# mSD-Shield_v20.net
KiCad netlist of a schematic drawn in EAGLE
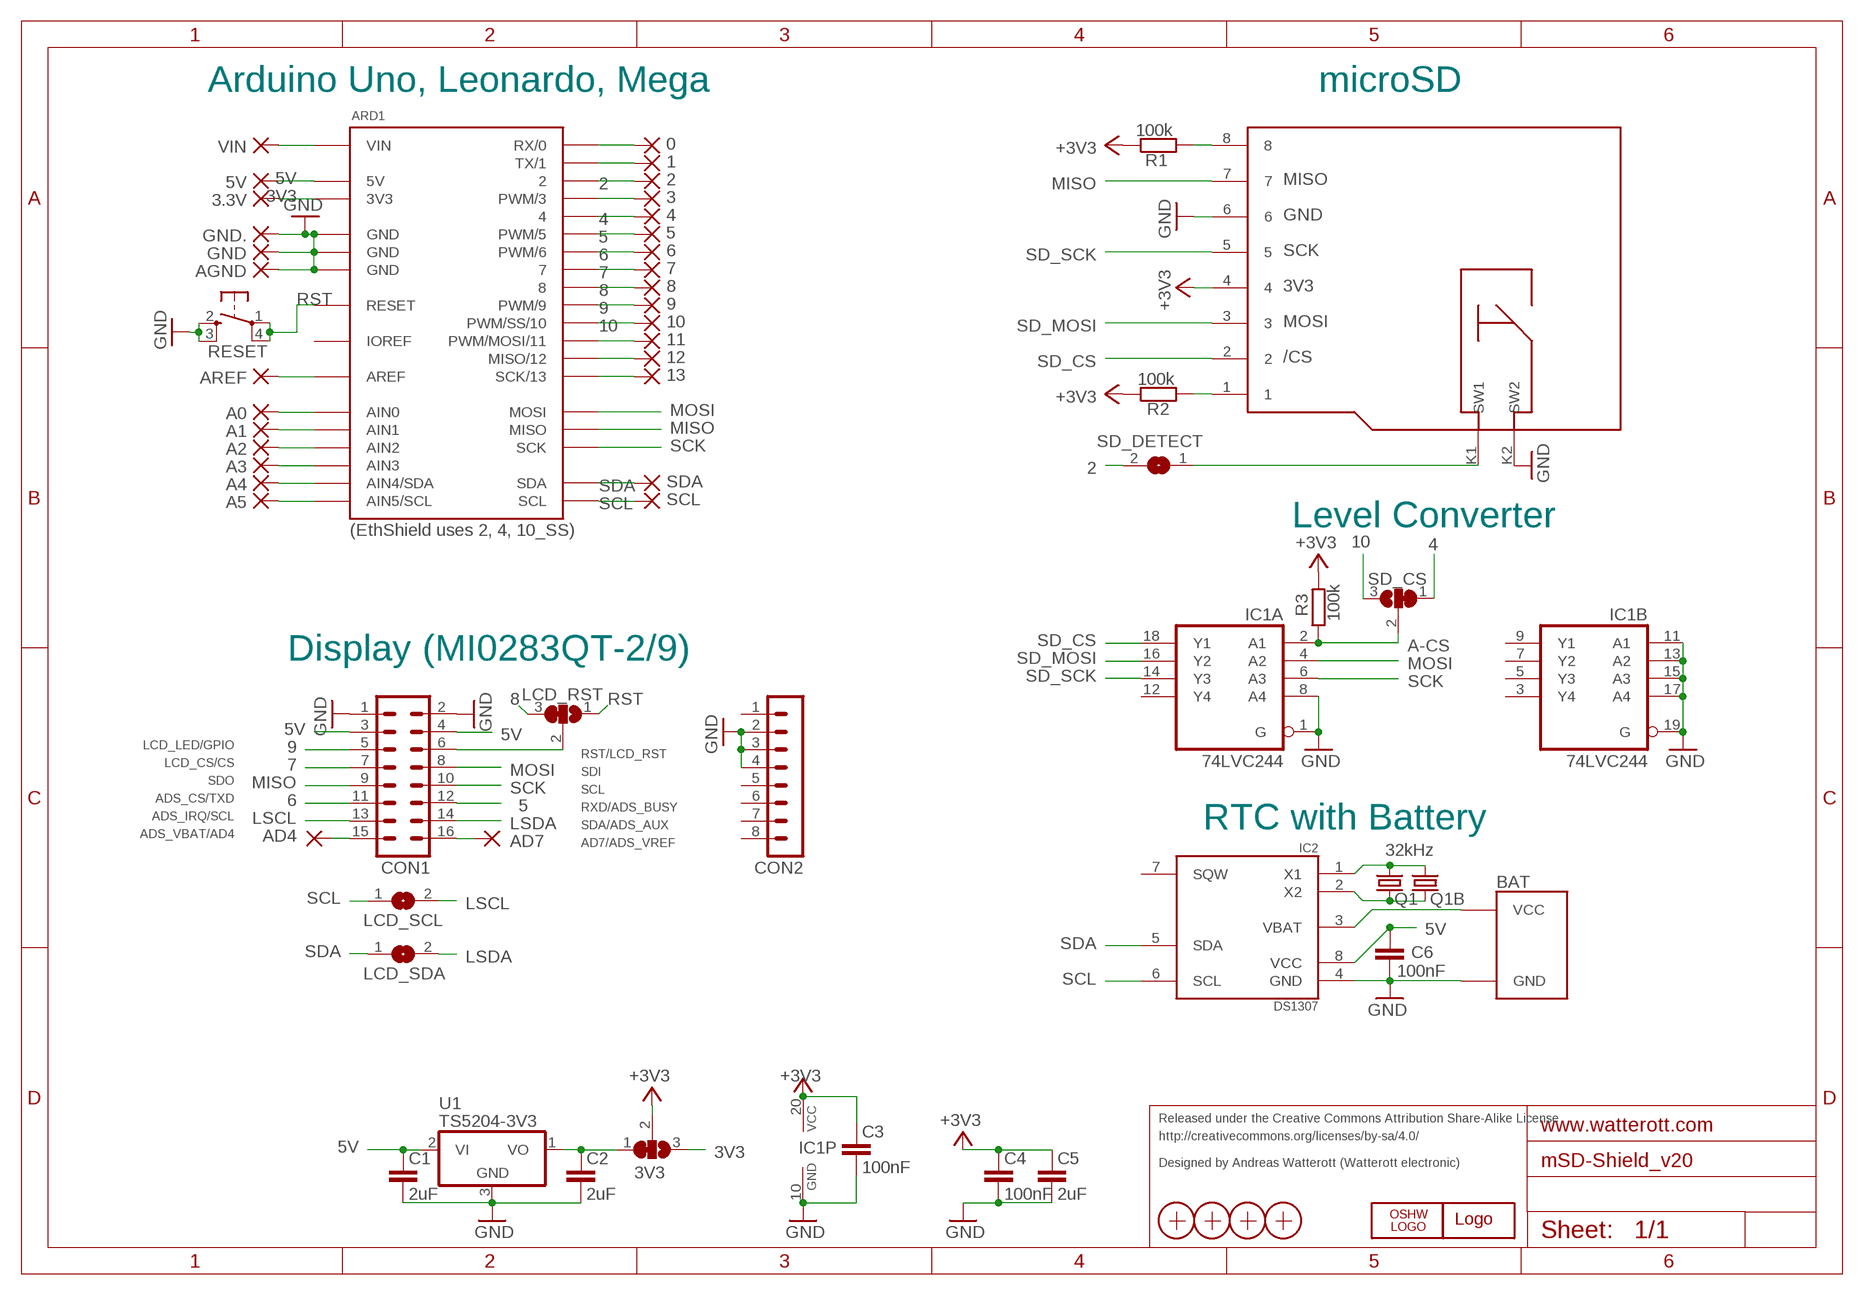
[diagram p0: schematic, sheet 1]

(export (version "E")
  (design (tool "Eeschema 10.0.6"))
  (components
    (comp (ref "0")
      (value "1,6/0,8")
      (footprint "eagle-import:1,6_0,8")
      (libsource (lib "eagle-import") (part "1,6/0,8"))
    )
    (comp (ref "1")
      (value "1,6/0,8")
      (footprint "eagle-import:1,6_0,8")
      (libsource (lib "eagle-import") (part "1,6/0,8"))
    )
    (comp (ref "2")
      (value "1,6/0,8")
      (footprint "eagle-import:1,6_0,8")
      (libsource (lib "eagle-import") (part "1,6/0,8"))
    )
    (comp (ref "3")
      (value "1,6/0,8")
      (footprint "eagle-import:1,6_0,8")
      (libsource (lib "eagle-import") (part "1,6/0,8"))
    )
    (comp (ref "3.3V")
      (value "1,6/0,8")
      (footprint "eagle-import:1,6_0,8")
      (libsource (lib "eagle-import") (part "1,6/0,8"))
    )
    (comp (ref "3V3")
      (value "SJ2W")
      (footprint "eagle-import:SJ_2")
      (libsource (lib "eagle-import") (part "SJ2W"))
    )
    (comp (ref "4")
      (value "1,6/0,8")
      (footprint "eagle-import:1,6_0,8")
      (libsource (lib "eagle-import") (part "1,6/0,8"))
    )
    (comp (ref "5")
      (value "1,6/0,8")
      (footprint "eagle-import:1,6_0,8")
      (libsource (lib "eagle-import") (part "1,6/0,8"))
    )
    (comp (ref "5V")
      (value "1,6/0,8")
      (footprint "eagle-import:1,6_0,8")
      (libsource (lib "eagle-import") (part "1,6/0,8"))
    )
    (comp (ref "6")
      (value "1,6/0,8")
      (footprint "eagle-import:1,6_0,8")
      (libsource (lib "eagle-import") (part "1,6/0,8"))
    )
    (comp (ref "7")
      (value "1,6/0,8")
      (footprint "eagle-import:1,6_0,8")
      (libsource (lib "eagle-import") (part "1,6/0,8"))
    )
    (comp (ref "8")
      (value "1,6/0,8")
      (footprint "eagle-import:1,6_0,8")
      (libsource (lib "eagle-import") (part "1,6/0,8"))
    )
    (comp (ref "9")
      (value "1,6/0,8")
      (footprint "eagle-import:1,6_0,8")
      (libsource (lib "eagle-import") (part "1,6/0,8"))
    )
    (comp (ref "10")
      (value "1,6/0,8")
      (footprint "eagle-import:1,6_0,8")
      (libsource (lib "eagle-import") (part "1,6/0,8"))
    )
    (comp (ref "11")
      (value "1,6/0,8")
      (footprint "eagle-import:1,6_0,8")
      (libsource (lib "eagle-import") (part "1,6/0,8"))
    )
    (comp (ref "12")
      (value "1,6/0,8")
      (footprint "eagle-import:1,6_0,8")
      (libsource (lib "eagle-import") (part "1,6/0,8"))
    )
    (comp (ref "13")
      (value "1,6/0,8")
      (footprint "eagle-import:1,6_0,8")
      (libsource (lib "eagle-import") (part "1,6/0,8"))
    )
    (comp (ref "A0")
      (value "1,6/0,8")
      (footprint "eagle-import:1,6_0,8")
      (libsource (lib "eagle-import") (part "1,6/0,8"))
    )
    (comp (ref "A1")
      (value "1,6/0,8")
      (footprint "eagle-import:1,6_0,8")
      (libsource (lib "eagle-import") (part "1,6/0,8"))
    )
    (comp (ref "A2")
      (value "1,6/0,8")
      (footprint "eagle-import:1,6_0,8")
      (libsource (lib "eagle-import") (part "1,6/0,8"))
    )
    (comp (ref "A3")
      (value "1,6/0,8")
      (footprint "eagle-import:1,6_0,8")
      (libsource (lib "eagle-import") (part "1,6/0,8"))
    )
    (comp (ref "A4")
      (value "1,6/0,8")
      (footprint "eagle-import:1,6_0,8")
      (libsource (lib "eagle-import") (part "1,6/0,8"))
    )
    (comp (ref "A5")
      (value "1,6/0,8")
      (footprint "eagle-import:1,6_0,8")
      (libsource (lib "eagle-import") (part "1,6/0,8"))
    )
    (comp (ref "AD4")
      (value "1,6/0,8")
      (footprint "eagle-import:1,6_0,8")
      (libsource (lib "eagle-import") (part "1,6/0,8"))
    )
    (comp (ref "AD7")
      (value "1,6/0,8")
      (footprint "eagle-import:1,6_0,8")
      (libsource (lib "eagle-import") (part "1,6/0,8"))
    )
    (comp (ref "AGND")
      (value "1,6/0,8")
      (footprint "eagle-import:1,6_0,8")
      (libsource (lib "eagle-import") (part "1,6/0,8"))
    )
    (comp (ref "ARD1")
      (value "UNO_ISP2")
      (footprint "eagle-import:UNO_ISP2")
      (libsource (lib "eagle-import") (part "UNO_ISP2"))
    )
    (comp (ref "AREF")
      (value "1,6/0,8")
      (footprint "eagle-import:1,6_0,8")
      (libsource (lib "eagle-import") (part "1,6/0,8"))
    )
    (comp (ref "BAT")
      (value "4UC-05581")
      (footprint "eagle-import:4UC-05581")
      (libsource (lib "eagle-import") (part "4UC-05581"))
    )
    (comp (ref "C1")
      (value "2uF")
      (footprint "eagle-import:C0805")
      (libsource (lib "eagle-import") (part "C-EUC0805"))
    )
    (comp (ref "C2")
      (value "2uF")
      (footprint "eagle-import:C0805")
      (libsource (lib "eagle-import") (part "C-EUC0805"))
    )
    (comp (ref "C3")
      (value "100nF")
      (footprint "eagle-import:C0603")
      (libsource (lib "eagle-import") (part "C-EUC0603"))
    )
    (comp (ref "C4")
      (value "100nF")
      (footprint "eagle-import:C0603")
      (libsource (lib "eagle-import") (part "C-EUC0603"))
    )
    (comp (ref "C5")
      (value "2uF")
      (footprint "eagle-import:C0603")
      (libsource (lib "eagle-import") (part "C-EUC0603"))
    )
    (comp (ref "C6")
      (value "100nF")
      (footprint "eagle-import:C0603")
      (libsource (lib "eagle-import") (part "C-EUC0603"))
    )
    (comp (ref "CON1")
      (value "MA08-2")
      (footprint "eagle-import:MA08-2")
      (libsource (lib "eagle-import") (part "MA08-2"))
    )
    (comp (ref "CON2")
      (value "MA08-1")
      (footprint "eagle-import:MA08-1")
      (libsource (lib "eagle-import") (part "MA08-1"))
    )
    (comp (ref "GND")
      (value "1,6/0,8")
      (footprint "eagle-import:1,6_0,8")
      (libsource (lib "eagle-import") (part "1,6/0,8"))
    )
    (comp (ref "GND.")
      (value "1,6/0,8")
      (footprint "eagle-import:1,6_0,8")
      (libsource (lib "eagle-import") (part "1,6/0,8"))
    )
    (comp (ref "IC1")
      (value "74LVC244")
      (footprint "eagle-import:SO20W")
      (libsource (lib "eagle-import") (part "74244DWHC"))
    )
    (comp (ref "IC2")
      (value "DS1307")
      (footprint "eagle-import:SO8")
      (libsource (lib "eagle-import") (part "DS1307"))
    )
    (comp (ref "LCD_RST")
      (value "SJ2W")
      (footprint "eagle-import:SJ_2")
      (libsource (lib "eagle-import") (part "SJ2W"))
    )
    (comp (ref "LCD_SCL")
      (value "SJ")
      (footprint "eagle-import:SJ")
      (libsource (lib "eagle-import") (part "SJ"))
    )
    (comp (ref "LCD_SDA")
      (value "SJ")
      (footprint "eagle-import:SJ")
      (libsource (lib "eagle-import") (part "SJ"))
    )
    (comp (ref "LOGO2")
      (value "WE-LOGOPLACE")
      (footprint "eagle-import:WE-LOGO")
      (libsource (lib "eagle-import") (part "WE-LOGOPLACE"))
    )
    (comp (ref "LOGO3")
      (value "OSHW_LOGO_6MILX0100-NT")
      (footprint "eagle-import:OSHW_6X100_NOTEXT")
      (libsource (lib "eagle-import") (part "OSHW_LOGO_6MILX0100-NT"))
    )
    (comp (ref "Q1")
      (value "32kHz")
      (footprint "eagle-import:TC26V")
      (libsource (lib "eagle-import") (part "CRYSTALTC26V"))
    )
    (comp (ref "Q1B")
      (value "32kHz")
      (footprint "eagle-import:ZM315")
      (libsource (lib "eagle-import") (part "CRYSTALZM315"))
    )
    (comp (ref "R1")
      (value "100k")
      (footprint "eagle-import:R0603")
      (libsource (lib "eagle-import") (part "R-EU_R0603"))
    )
    (comp (ref "R2")
      (value "100k")
      (footprint "eagle-import:R0603")
      (libsource (lib "eagle-import") (part "R-EU_R0603"))
    )
    (comp (ref "R3")
      (value "100k")
      (footprint "eagle-import:R0603")
      (libsource (lib "eagle-import") (part "R-EU_R0603"))
    )
    (comp (ref "RESET")
      (value "SW4S")
      (footprint "eagle-import:SW_SMD4")
      (libsource (lib "eagle-import") (part "SW4S"))
    )
    (comp (ref "SCL")
      (value "1,6/0,8")
      (footprint "eagle-import:1,6_0,8")
      (libsource (lib "eagle-import") (part "1,6/0,8"))
    )
    (comp (ref "SDA")
      (value "1,6/0,8")
      (footprint "eagle-import:1,6_0,8")
      (libsource (lib "eagle-import") (part "1,6/0,8"))
    )
    (comp (ref "SD_CS")
      (value "SJ2W")
      (footprint "eagle-import:SJ_2")
      (libsource (lib "eagle-import") (part "SJ2W"))
    )
    (comp (ref "SD_DETECT")
      (value "SJ")
      (footprint "eagle-import:SJ")
      (libsource (lib "eagle-import") (part "SJ"))
    )
    (comp (ref "U1")
      (value "TS5204-3V3")
      (footprint "eagle-import:SOT23")
      (libsource (lib "eagle-import") (part "TS5204"))
    )
    (comp (ref "VIN")
      (value "1,6/0,8")
      (footprint "eagle-import:1,6_0,8")
      (libsource (lib "eagle-import") (part "1,6/0,8"))
    )
    (comp (ref "X1")
      (value "PASSER")
      (footprint "eagle-import:PASSER")
      (libsource (lib "eagle-import") (part "PASSER"))
    )
    (comp (ref "X2")
      (value "PASSER")
      (footprint "eagle-import:PASSER")
      (libsource (lib "eagle-import") (part "PASSER"))
    )
    (comp (ref "X3")
      (value "PASSER")
      (footprint "eagle-import:PASSER")
      (libsource (lib "eagle-import") (part "PASSER"))
    )
    (comp (ref "X4")
      (value "PASSER")
      (footprint "eagle-import:PASSER")
      (libsource (lib "eagle-import") (part "PASSER"))
    )
    (comp (ref "X5")
      (value "MICRO-SD")
      (footprint "eagle-import:MICRO-SD")
      (libsource (lib "eagle-import") (part "MICRO-SD"))
    )
  )
  (nets
    (net (code "1") (name "+3V3") (class "Default")
      (node (ref "3V3") (pin "2") (pinfunction "2_2") (pintype "passive"))
      (node (ref "C3") (pin "1") (pinfunction "1_1") (pintype "passive"))
      (node (ref "C4") (pin "1") (pinfunction "1_1") (pintype "passive"))
      (node (ref "C5") (pin "1") (pinfunction "1_1") (pintype "passive"))
      (node (ref "IC1") (pin "20") (pinfunction "VCC_20") (pintype "power_in"))
      (node (ref "R1") (pin "1") (pinfunction "1_1") (pintype "passive"))
      (node (ref "R2") (pin "1") (pinfunction "1_1") (pintype "passive"))
      (node (ref "R3") (pin "2") (pinfunction "2_2") (pintype "passive"))
      (node (ref "X5") (pin "4") (pinfunction "4_4") (pintype "bidirectional"))
    )
    (net (code "2") (name "/2") (class "Default")
      (node (ref "2") (pin "1") (pinfunction "P_1") (pintype "passive"))
      (node (ref "ARD1") (pin "2") (pinfunction "2_2") (pintype "bidirectional"))
      (node (ref "SD_DETECT") (pin "2") (pinfunction "2_2") (pintype "passive"))
    )
    (net (code "3") (name "/3V3") (class "Default")
      (node (ref "3.3V") (pin "1") (pinfunction "P_1") (pintype "passive"))
      (node (ref "3V3") (pin "3") (pinfunction "3_3") (pintype "passive"))
      (node (ref "ARD1") (pin "3V3") (pinfunction "3V3_3V3") (pintype "power_in"))
    )
    (net (code "4") (name "/4") (class "Default")
      (node (ref "4") (pin "1") (pinfunction "P_1") (pintype "passive"))
      (node (ref "ARD1") (pin "4") (pinfunction "4_4") (pintype "bidirectional"))
      (node (ref "SD_CS") (pin "1") (pinfunction "1_1") (pintype "passive"))
    )
    (net (code "5") (name "/5") (class "Default")
      (node (ref "5") (pin "1") (pinfunction "P_1") (pintype "passive"))
      (node (ref "ARD1") (pin "5") (pinfunction "PWM/5_5") (pintype "bidirectional"))
      (node (ref "CON1") (pin "12") (pinfunction "12_12") (pintype "passive"))
    )
    (net (code "6") (name "/5V") (class "Default")
      (node (ref "5V") (pin "1") (pinfunction "P_1") (pintype "passive"))
      (node (ref "ARD1") (pin "5V") (pinfunction "5V_5V") (pintype "power_in"))
      (node (ref "C1") (pin "1") (pinfunction "1_1") (pintype "passive"))
      (node (ref "C6") (pin "2") (pinfunction "2_2") (pintype "passive"))
      (node (ref "CON1") (pin "3") (pinfunction "3_3") (pintype "passive"))
      (node (ref "CON1") (pin "4") (pinfunction "4_4") (pintype "passive"))
      (node (ref "IC2") (pin "8") (pinfunction "VCC_8") (pintype "power_in"))
      (node (ref "U1") (pin "2") (pinfunction "VI_2") (pintype "input"))
    )
    (net (code "7") (name "/6") (class "Default")
      (node (ref "6") (pin "1") (pinfunction "P_1") (pintype "passive"))
      (node (ref "ARD1") (pin "6") (pinfunction "PWM/6_6") (pintype "bidirectional"))
      (node (ref "CON1") (pin "11") (pinfunction "11_11") (pintype "passive"))
    )
    (net (code "8") (name "/7") (class "Default")
      (node (ref "7") (pin "1") (pinfunction "P_1") (pintype "passive"))
      (node (ref "ARD1") (pin "7") (pinfunction "7_7") (pintype "bidirectional"))
      (node (ref "CON1") (pin "7") (pinfunction "7_7") (pintype "passive"))
    )
    (net (code "9") (name "/8") (class "Default")
      (node (ref "8") (pin "1") (pinfunction "P_1") (pintype "passive"))
      (node (ref "ARD1") (pin "8") (pinfunction "8_8") (pintype "bidirectional"))
      (node (ref "LCD_RST") (pin "3") (pinfunction "3_3") (pintype "passive"))
    )
    (net (code "10") (name "/9") (class "Default")
      (node (ref "9") (pin "1") (pinfunction "P_1") (pintype "passive"))
      (node (ref "ARD1") (pin "9") (pinfunction "PWM/9_9") (pintype "bidirectional"))
      (node (ref "CON1") (pin "5") (pinfunction "5_5") (pintype "passive"))
    )
    (net (code "11") (name "/10") (class "Default")
      (node (ref "10") (pin "1") (pinfunction "P_1") (pintype "passive"))
      (node (ref "ARD1") (pin "10") (pinfunction "PWM/SS/10_10") (pintype "bidirectional"))
      (node (ref "SD_CS") (pin "3") (pinfunction "3_3") (pintype "passive"))
    )
    (net (code "12") (name "/A-CS") (class "Default")
      (node (ref "IC1") (pin "2") (pinfunction "A1_2") (pintype "input"))
      (node (ref "R3") (pin "1") (pinfunction "1_1") (pintype "passive"))
      (node (ref "SD_CS") (pin "2") (pinfunction "2_2") (pintype "passive"))
    )
    (net (code "13") (name "/IOREF") (class "Default")
      (node (ref "ARD1") (pin "IOREF") (pinfunction "IOREF_IOREF") (pintype "power_in"))
    )
    (net (code "14") (name "/LSCL") (class "Default")
      (node (ref "CON1") (pin "13") (pinfunction "13_13") (pintype "passive"))
      (node (ref "LCD_SCL") (pin "2") (pinfunction "2_2") (pintype "passive"))
    )
    (net (code "15") (name "/LSDA") (class "Default")
      (node (ref "CON1") (pin "14") (pinfunction "14_14") (pintype "passive"))
      (node (ref "LCD_SDA") (pin "2") (pinfunction "2_2") (pintype "passive"))
    )
    (net (code "16") (name "/MISO") (class "Default")
      (node (ref "ARD1") (pin "MISO") (pinfunction "MISO_MISO") (pintype "bidirectional"))
      (node (ref "CON1") (pin "9") (pinfunction "9_9") (pintype "passive"))
      (node (ref "X5") (pin "7") (pinfunction "7_7") (pintype "bidirectional"))
    )
    (net (code "17") (name "/MOSI") (class "Default")
      (node (ref "ARD1") (pin "MOSI") (pinfunction "MOSI_MOSI") (pintype "bidirectional"))
      (node (ref "CON1") (pin "8") (pinfunction "8_8") (pintype "passive"))
      (node (ref "IC1") (pin "4") (pinfunction "A2_4") (pintype "input"))
    )
    (net (code "18") (name "/RST") (class "Default")
      (node (ref "ARD1") (pin "RST") (pinfunction "RESET_RST") (pintype "bidirectional"))
      (node (ref "LCD_RST") (pin "1") (pinfunction "1_1") (pintype "passive"))
      (node (ref "RESET") (pin "1") (pinfunction "P_1") (pintype "passive"))
      (node (ref "RESET") (pin "4") (pinfunction "P1_4") (pintype "passive"))
    )
    (net (code "19") (name "/SCK") (class "Default")
      (node (ref "ARD1") (pin "SCK") (pinfunction "SCK_SCK") (pintype "bidirectional"))
      (node (ref "CON1") (pin "10") (pinfunction "10_10") (pintype "passive"))
      (node (ref "IC1") (pin "6") (pinfunction "A3_6") (pintype "input"))
    )
    (net (code "20") (name "/SCL") (class "Default")
      (node (ref "ARD1") (pin "SCL") (pinfunction "SCL_SCL") (pintype "bidirectional"))
      (node (ref "IC2") (pin "6") (pinfunction "SCL_6") (pintype "bidirectional"))
      (node (ref "LCD_SCL") (pin "1") (pinfunction "1_1") (pintype "passive"))
      (node (ref "SCL") (pin "1") (pinfunction "P_1") (pintype "passive"))
    )
    (net (code "21") (name "/SDA") (class "Default")
      (node (ref "ARD1") (pin "SDA") (pinfunction "SDA_SDA") (pintype "bidirectional"))
      (node (ref "IC2") (pin "5") (pinfunction "SDA_5") (pintype "bidirectional"))
      (node (ref "LCD_SDA") (pin "1") (pinfunction "1_1") (pintype "passive"))
      (node (ref "SDA") (pin "1") (pinfunction "P_1") (pintype "passive"))
    )
    (net (code "22") (name "/SD_CS") (class "Default")
      (node (ref "IC1") (pin "18") (pinfunction "Y1_18") (pintype "tri_state"))
      (node (ref "X5") (pin "2") (pinfunction "2_2") (pintype "bidirectional"))
    )
    (net (code "23") (name "/SD_MOSI") (class "Default")
      (node (ref "IC1") (pin "16") (pinfunction "Y2_16") (pintype "tri_state"))
      (node (ref "X5") (pin "3") (pinfunction "3_3") (pintype "bidirectional"))
    )
    (net (code "24") (name "/SD_SCK") (class "Default")
      (node (ref "IC1") (pin "14") (pinfunction "Y3_14") (pintype "tri_state"))
      (node (ref "X5") (pin "5") (pinfunction "5_5") (pintype "bidirectional"))
    )
    (net (code "25") (name "GND") (class "Default")
      (node (ref "AGND") (pin "1") (pinfunction "P_1") (pintype "passive"))
      (node (ref "ARD1") (pin "GND@1") (pinfunction "GND_GND@1") (pintype "power_in"))
      (node (ref "ARD1") (pin "GND@2") (pinfunction "GND_GND@2") (pintype "power_in"))
      (node (ref "ARD1") (pin "GND@3") (pinfunction "GND_GND@3") (pintype "power_in"))
      (node (ref "BAT") (pin "GND") (pinfunction "GND_GND") (pintype "power_in"))
      (node (ref "C1") (pin "2") (pinfunction "2_2") (pintype "passive"))
      (node (ref "C2") (pin "2") (pinfunction "2_2") (pintype "passive"))
      (node (ref "C3") (pin "2") (pinfunction "2_2") (pintype "passive"))
      (node (ref "C4") (pin "2") (pinfunction "2_2") (pintype "passive"))
      (node (ref "C5") (pin "2") (pinfunction "2_2") (pintype "passive"))
      (node (ref "C6") (pin "1") (pinfunction "1_1") (pintype "passive"))
      (node (ref "CON1") (pin "1") (pinfunction "1_1") (pintype "passive"))
      (node (ref "CON1") (pin "2") (pinfunction "2_2") (pintype "passive"))
      (node (ref "CON2") (pin "2") (pinfunction "2_2") (pintype "passive"))
      (node (ref "CON2") (pin "3") (pinfunction "3_3") (pintype "passive"))
      (node (ref "CON2") (pin "4") (pinfunction "4_4") (pintype "passive"))
      (node (ref "GND") (pin "1") (pinfunction "P_1") (pintype "passive"))
      (node (ref "GND.") (pin "1") (pinfunction "P_1") (pintype "passive"))
      (node (ref "IC1") (pin "1") (pinfunction "G_1") (pintype "input"))
      (node (ref "IC1") (pin "10") (pinfunction "GND_10") (pintype "power_in"))
      (node (ref "IC1") (pin "11") (pinfunction "A1_11") (pintype "input"))
      (node (ref "IC1") (pin "13") (pinfunction "A2_13") (pintype "input"))
      (node (ref "IC1") (pin "15") (pinfunction "A3_15") (pintype "input"))
      (node (ref "IC1") (pin "17") (pinfunction "A4_17") (pintype "input"))
      (node (ref "IC1") (pin "19") (pinfunction "G_19") (pintype "input"))
      (node (ref "IC1") (pin "8") (pinfunction "A4_8") (pintype "input"))
      (node (ref "IC2") (pin "4") (pinfunction "GND_4") (pintype "power_in"))
      (node (ref "RESET") (pin "2") (pinfunction "S_2") (pintype "passive"))
      (node (ref "RESET") (pin "3") (pinfunction "S1_3") (pintype "passive"))
      (node (ref "U1") (pin "3") (pinfunction "GND_3") (pintype "passive"))
      (node (ref "X5") (pin "6") (pinfunction "6_6") (pintype "bidirectional"))
      (node (ref "X5") (pin "K2") (pinfunction "SW2_K2") (pintype "bidirectional"))
    )
    (net (code "26") (name "Net-(0-P)") (class "Default")
      (node (ref "0") (pin "1") (pinfunction "P_1") (pintype "passive"))
      (node (ref "ARD1") (pin "0") (pinfunction "RX/0_0") (pintype "bidirectional"))
    )
    (net (code "27") (name "Net-(1-P)") (class "Default")
      (node (ref "1") (pin "1") (pinfunction "P_1") (pintype "passive"))
      (node (ref "ARD1") (pin "1") (pinfunction "TX/1_1") (pintype "bidirectional"))
    )
    (net (code "28") (name "Net-(3-P)") (class "Default")
      (node (ref "3") (pin "1") (pinfunction "P_1") (pintype "passive"))
      (node (ref "ARD1") (pin "3") (pinfunction "PWM/3_3") (pintype "bidirectional"))
    )
    (net (code "29") (name "Net-(11-P)") (class "Default")
      (node (ref "11") (pin "1") (pinfunction "P_1") (pintype "passive"))
      (node (ref "ARD1") (pin "11") (pinfunction "PWM/MOSI/11_11") (pintype "bidirectional"))
    )
    (net (code "30") (name "Net-(12-P)") (class "Default")
      (node (ref "12") (pin "1") (pinfunction "P_1") (pintype "passive"))
      (node (ref "ARD1") (pin "12") (pinfunction "MISO/12_12") (pintype "bidirectional"))
    )
    (net (code "31") (name "Net-(13-P)") (class "Default")
      (node (ref "13") (pin "1") (pinfunction "P_1") (pintype "passive"))
      (node (ref "ARD1") (pin "13") (pinfunction "SCK/13_13") (pintype "bidirectional"))
    )
    (net (code "32") (name "Net-(A0-P)") (class "Default")
      (node (ref "A0") (pin "1") (pinfunction "P_1") (pintype "passive"))
      (node (ref "ARD1") (pin "AIN0") (pinfunction "AIN0_AIN0") (pintype "bidirectional"))
    )
    (net (code "33") (name "Net-(A1-P)") (class "Default")
      (node (ref "A1") (pin "1") (pinfunction "P_1") (pintype "passive"))
      (node (ref "ARD1") (pin "AIN1") (pinfunction "AIN1_AIN1") (pintype "bidirectional"))
    )
    (net (code "34") (name "Net-(A2-P)") (class "Default")
      (node (ref "A2") (pin "1") (pinfunction "P_1") (pintype "passive"))
      (node (ref "ARD1") (pin "AIN2") (pinfunction "AIN2_AIN2") (pintype "bidirectional"))
    )
    (net (code "35") (name "Net-(A3-P)") (class "Default")
      (node (ref "A3") (pin "1") (pinfunction "P_1") (pintype "passive"))
      (node (ref "ARD1") (pin "AIN3") (pinfunction "AIN3_AIN3") (pintype "bidirectional"))
    )
    (net (code "36") (name "Net-(A4-P)") (class "Default")
      (node (ref "A4") (pin "1") (pinfunction "P_1") (pintype "passive"))
      (node (ref "ARD1") (pin "AIN4") (pinfunction "AIN4/SDA_AIN4") (pintype "bidirectional"))
    )
    (net (code "37") (name "Net-(A5-P)") (class "Default")
      (node (ref "A5") (pin "1") (pinfunction "P_1") (pintype "passive"))
      (node (ref "ARD1") (pin "AIN5") (pinfunction "AIN5/SCL_AIN5") (pintype "bidirectional"))
    )
    (net (code "38") (name "Net-(AD4-P)") (class "Default")
      (node (ref "AD4") (pin "1") (pinfunction "P_1") (pintype "passive"))
      (node (ref "CON1") (pin "15") (pinfunction "15_15") (pintype "passive"))
    )
    (net (code "39") (name "Net-(AD7-P)") (class "Default")
      (node (ref "AD7") (pin "1") (pinfunction "P_1") (pintype "passive"))
      (node (ref "CON1") (pin "16") (pinfunction "16_16") (pintype "passive"))
    )
    (net (code "40") (name "Net-(AREF-P)") (class "Default")
      (node (ref "ARD1") (pin "AREF") (pinfunction "AREF_AREF") (pintype "power_in"))
      (node (ref "AREF") (pin "1") (pinfunction "P_1") (pintype "passive"))
    )
    (net (code "41") (name "Net-(CON1-Pad6)") (class "Default")
      (node (ref "CON1") (pin "6") (pinfunction "6_6") (pintype "passive"))
      (node (ref "LCD_RST") (pin "2") (pinfunction "2_2") (pintype "passive"))
    )
    (net (code "42") (name "Net-(IC2-VBAT)") (class "Default")
      (node (ref "BAT") (pin "VCC") (pinfunction "VCC_VCC") (pintype "power_in"))
      (node (ref "IC2") (pin "3") (pinfunction "VBAT_3") (pintype "power_in"))
    )
    (net (code "43") (name "Net-(IC2-X1)") (class "Default")
      (node (ref "IC2") (pin "1") (pinfunction "X1_1") (pintype "bidirectional"))
      (node (ref "Q1") (pin "2") (pinfunction "2_2") (pintype "passive"))
      (node (ref "Q1B") (pin "2") (pinfunction "2_2") (pintype "passive"))
    )
    (net (code "44") (name "Net-(IC2-X2)") (class "Default")
      (node (ref "IC2") (pin "2") (pinfunction "X2_2") (pintype "bidirectional"))
      (node (ref "Q1") (pin "1") (pinfunction "1_1") (pintype "passive"))
      (node (ref "Q1B") (pin "1") (pinfunction "1_1") (pintype "passive"))
    )
    (net (code "45") (name "Net-(R1-Pad2)") (class "Default")
      (node (ref "R1") (pin "2") (pinfunction "2_2") (pintype "passive"))
      (node (ref "X5") (pin "8") (pinfunction "8_8") (pintype "bidirectional"))
    )
    (net (code "46") (name "Net-(R2-Pad2)") (class "Default")
      (node (ref "R2") (pin "2") (pinfunction "2_2") (pintype "passive"))
      (node (ref "X5") (pin "1") (pinfunction "1_1") (pintype "bidirectional"))
    )
    (net (code "47") (name "Net-(U1-VO)") (class "Default")
      (node (ref "3V3") (pin "1") (pinfunction "1_1") (pintype "passive"))
      (node (ref "C2") (pin "1") (pinfunction "1_1") (pintype "passive"))
      (node (ref "U1") (pin "1") (pinfunction "VO_1") (pintype "passive"))
    )
    (net (code "48") (name "Net-(VIN-P)") (class "Default")
      (node (ref "ARD1") (pin "VIN") (pinfunction "VIN_VIN") (pintype "power_in"))
      (node (ref "VIN") (pin "1") (pinfunction "P_1") (pintype "passive"))
    )
    (net (code "49") (name "Net-(X5-SW1)") (class "Default")
      (node (ref "SD_DETECT") (pin "1") (pinfunction "1_1") (pintype "passive"))
      (node (ref "X5") (pin "K1") (pinfunction "SW1_K1") (pintype "bidirectional"))
    )
    (net (code "50") (name "unconnected-(CON2-Pad1)") (class "Default")
      (node (ref "CON2") (pin "1") (pinfunction "1_1") (pintype "passive"))
    )
    (net (code "51") (name "unconnected-(CON2-Pad5)") (class "Default")
      (node (ref "CON2") (pin "5") (pinfunction "5_5") (pintype "passive"))
    )
    (net (code "52") (name "unconnected-(CON2-Pad6)") (class "Default")
      (node (ref "CON2") (pin "6") (pinfunction "6_6") (pintype "passive"))
    )
    (net (code "53") (name "unconnected-(CON2-Pad7)") (class "Default")
      (node (ref "CON2") (pin "7") (pinfunction "7_7") (pintype "passive"))
    )
    (net (code "54") (name "unconnected-(CON2-Pad8)") (class "Default")
      (node (ref "CON2") (pin "8") (pinfunction "8_8") (pintype "passive"))
    )
    (net (code "55") (name "unconnected-(IC1A-Y4-Pad12)") (class "Default")
      (node (ref "IC1") (pin "12") (pinfunction "Y4_12") (pintype "tri_state"))
    )
    (net (code "56") (name "unconnected-(IC1B-Y1-Pad9)") (class "Default")
      (node (ref "IC1") (pin "9") (pinfunction "Y1_9") (pintype "tri_state"))
    )
    (net (code "57") (name "unconnected-(IC1B-Y2-Pad7)") (class "Default")
      (node (ref "IC1") (pin "7") (pinfunction "Y2_7") (pintype "tri_state"))
    )
    (net (code "58") (name "unconnected-(IC1B-Y3-Pad5)") (class "Default")
      (node (ref "IC1") (pin "5") (pinfunction "Y3_5") (pintype "tri_state"))
    )
    (net (code "59") (name "unconnected-(IC1B-Y4-Pad3)") (class "Default")
      (node (ref "IC1") (pin "3") (pinfunction "Y4_3") (pintype "tri_state"))
    )
    (net (code "60") (name "unconnected-(IC2-SQW-Pad7)") (class "Default")
      (node (ref "IC2") (pin "7") (pinfunction "SQW_7") (pintype "bidirectional"))
    )
  )
)
